# CAN-Bus.net
KiCad netlist of a schematic drawn in EAGLE
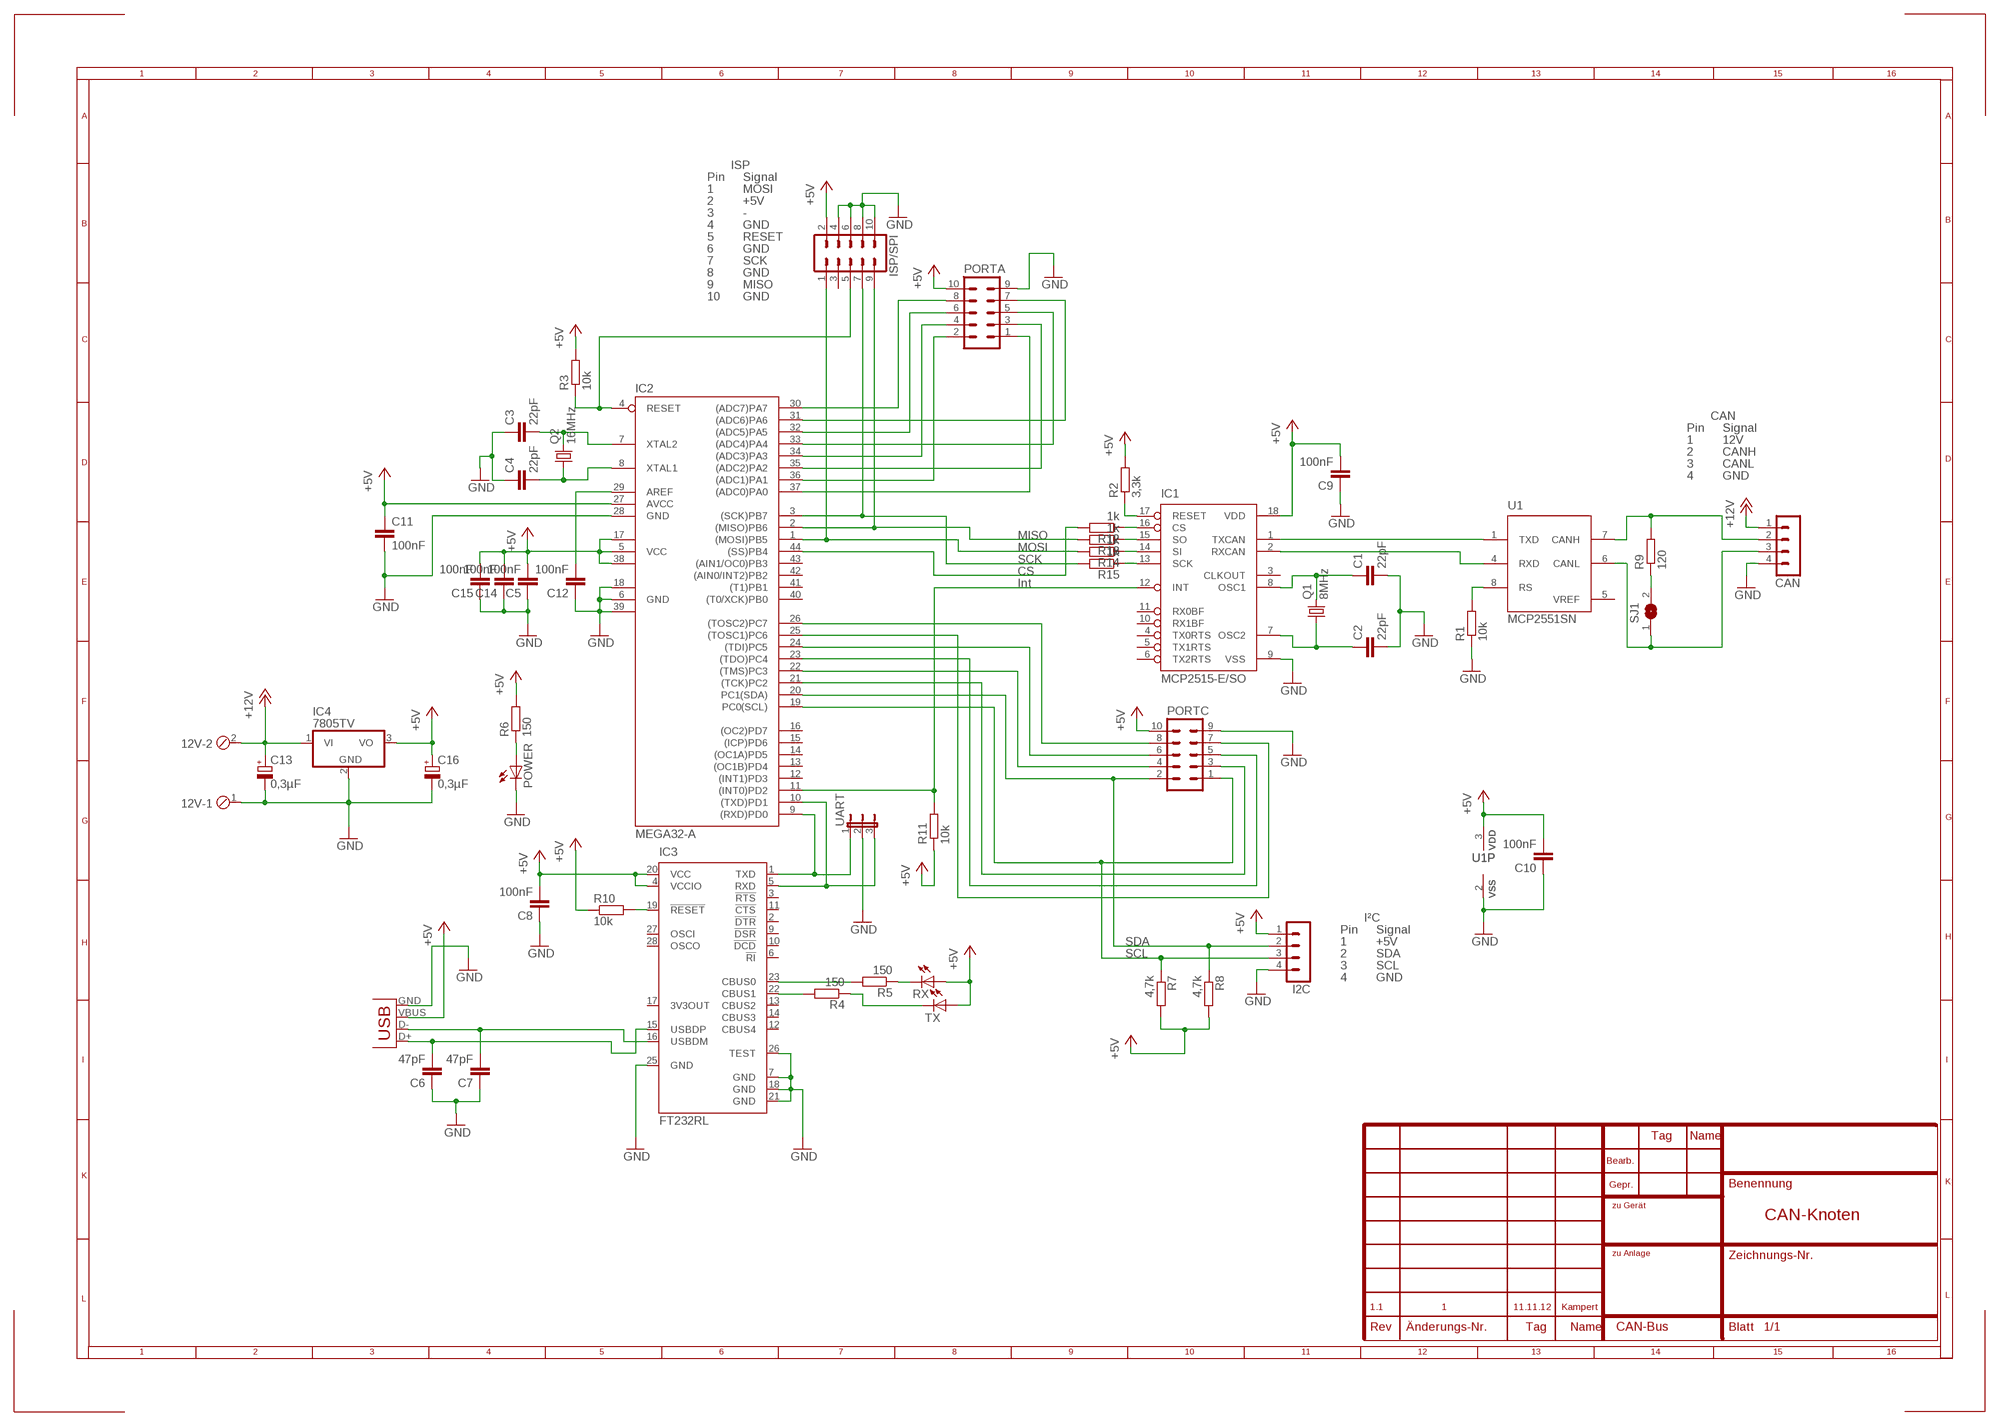
[diagram p0: schematic, sheet 1]

(export (version "E")
  (design (tool "Eeschema 10.0.6"))
  (components
    (comp (ref "12V")
      (value "MPT2")
      (footprint "eagle-import:2POL254")
      (libsource (lib "eagle-import") (part "MPT2"))
    )
    (comp (ref "C1")
      (value "22pF")
      (footprint "eagle-import:C0805")
      (libsource (lib "eagle-import") (part "C-EUC0805"))
    )
    (comp (ref "C2")
      (value "22pF")
      (footprint "eagle-import:C0805")
      (libsource (lib "eagle-import") (part "C-EUC0805"))
    )
    (comp (ref "C3")
      (value "22pF")
      (footprint "eagle-import:C0805")
      (libsource (lib "eagle-import") (part "C-EUC0805"))
    )
    (comp (ref "C4")
      (value "22pF")
      (footprint "eagle-import:C0805")
      (libsource (lib "eagle-import") (part "C-EUC0805"))
    )
    (comp (ref "C5")
      (value "100nF")
      (footprint "eagle-import:C0805")
      (libsource (lib "eagle-import") (part "C-EUC0805"))
    )
    (comp (ref "C6")
      (value "47pF")
      (footprint "eagle-import:C0805")
      (libsource (lib "eagle-import") (part "C-EUC0805"))
    )
    (comp (ref "C7")
      (value "47pF")
      (footprint "eagle-import:C0805")
      (libsource (lib "eagle-import") (part "C-EUC0805"))
    )
    (comp (ref "C8")
      (value "100nF")
      (footprint "eagle-import:C0805")
      (libsource (lib "eagle-import") (part "C-EUC0805"))
    )
    (comp (ref "C9")
      (value "100nF")
      (footprint "eagle-import:C0805")
      (libsource (lib "eagle-import") (part "C-EUC0805"))
    )
    (comp (ref "C10")
      (value "100nF")
      (footprint "eagle-import:C0805")
      (libsource (lib "eagle-import") (part "C-EUC0805"))
    )
    (comp (ref "C11")
      (value "100nF")
      (footprint "eagle-import:C0805")
      (libsource (lib "eagle-import") (part "C-EUC0805"))
    )
    (comp (ref "C12")
      (value "100nF")
      (footprint "eagle-import:C0805")
      (libsource (lib "eagle-import") (part "C-EUC0805"))
    )
    (comp (ref "C13")
      (value "0,3µF")
      (footprint "eagle-import:153CLV-0405")
      (libsource (lib "eagle-import") (part "CPOL-EU153CLV-0405"))
    )
    (comp (ref "C14")
      (value "100nF")
      (footprint "eagle-import:C0805")
      (libsource (lib "eagle-import") (part "C-EUC0805"))
    )
    (comp (ref "C15")
      (value "100nF")
      (footprint "eagle-import:C0805")
      (libsource (lib "eagle-import") (part "C-EUC0805"))
    )
    (comp (ref "C16")
      (value "0,3µF")
      (footprint "eagle-import:153CLV-0405")
      (libsource (lib "eagle-import") (part "CPOL-EU153CLV-0405"))
    )
    (comp (ref "CAN")
      (value "MA04-1")
      (footprint "eagle-import:MA04-1")
      (libsource (lib "eagle-import") (part "MA04-1"))
    )
    (comp (ref "I2C")
      (value "MA04-1")
      (footprint "eagle-import:MA04-1")
      (fields (field (name "OC_FARNELL") "unknown") (field (name "OC_NEWARK") "unknown"))
      (libsource (lib "eagle-import") (part "MA04-1"))
    )
    (comp (ref "IC1")
      (value "MCP2515-E/SO")
      (footprint "eagle-import:SO18L")
      (libsource (lib "eagle-import") (part "MCP2515-E/SO"))
    )
    (comp (ref "IC2")
      (value "MEGA32-A")
      (footprint "eagle-import:TQFP44")
      (fields (field (name "MPN") "ATMEGA32-16AU"))
      (libsource (lib "eagle-import") (part "MEGA32-A"))
    )
    (comp (ref "IC3")
      (value "FT232RL")
      (footprint "eagle-import:SSOP28")
      (libsource (lib "eagle-import") (part "FT232RL"))
    )
    (comp (ref "IC4")
      (value "7805TV")
      (footprint "eagle-import:TO220V")
      (libsource (lib "eagle-import") (part "78TV05"))
    )
    (comp (ref "ISP/SPI")
      (value "ML10")
      (footprint "eagle-import:ML10")
      (libsource (lib "eagle-import") (part "ML10"))
    )
    (comp (ref "PORTA")
      (value "ML10")
      (footprint "eagle-import:ML10")
      (fields (field (name "OC_FARNELL") "unknown") (field (name "OC_NEWARK") "unknown"))
      (libsource (lib "eagle-import") (part "ML10"))
    )
    (comp (ref "PORTC")
      (value "ML10")
      (footprint "eagle-import:ML10")
      (fields (field (name "OC_FARNELL") "unknown") (field (name "OC_NEWARK") "unknown"))
      (libsource (lib "eagle-import") (part "ML10"))
    )
    (comp (ref "POWER")
      (value "LEDCHIP-LED0805")
      (footprint "eagle-import:CHIP-LED0805")
      (libsource (lib "eagle-import") (part "LEDCHIP-LED0805"))
    )
    (comp (ref "Q1")
      (value "8MHz")
      (footprint "eagle-import:HC49UP")
      (libsource (lib "eagle-import") (part "CRYSTALHC49UP"))
    )
    (comp (ref "Q2")
      (value "16MHz")
      (footprint "eagle-import:HC49UP")
      (libsource (lib "eagle-import") (part "CRYSTALHC49UP"))
    )
    (comp (ref "R1")
      (value "10k")
      (footprint "eagle-import:M0805")
      (libsource (lib "eagle-import") (part "R-EU_M0805"))
    )
    (comp (ref "R2")
      (value "3,3k")
      (footprint "eagle-import:M0805")
      (libsource (lib "eagle-import") (part "R-EU_M0805"))
    )
    (comp (ref "R3")
      (value "10k")
      (footprint "eagle-import:M0805")
      (libsource (lib "eagle-import") (part "R-EU_M0805"))
    )
    (comp (ref "R4")
      (value "150")
      (footprint "eagle-import:M0805")
      (libsource (lib "eagle-import") (part "R-EU_M0805"))
    )
    (comp (ref "R5")
      (value "150")
      (footprint "eagle-import:M0805")
      (libsource (lib "eagle-import") (part "R-EU_M0805"))
    )
    (comp (ref "R6")
      (value "150")
      (footprint "eagle-import:M0805")
      (libsource (lib "eagle-import") (part "R-EU_M0805"))
    )
    (comp (ref "R7")
      (value "4,7k")
      (footprint "eagle-import:M0805")
      (libsource (lib "eagle-import") (part "R-EU_M0805"))
    )
    (comp (ref "R8")
      (value "4,7k")
      (footprint "eagle-import:M0805")
      (libsource (lib "eagle-import") (part "R-EU_M0805"))
    )
    (comp (ref "R9")
      (value "120")
      (footprint "eagle-import:M0805")
      (libsource (lib "eagle-import") (part "R-EU_M0805"))
    )
    (comp (ref "R10")
      (value "10k")
      (footprint "eagle-import:M0805")
      (libsource (lib "eagle-import") (part "R-EU_M0805"))
    )
    (comp (ref "R11")
      (value "10k")
      (footprint "eagle-import:M0805")
      (libsource (lib "eagle-import") (part "R-EU_M0805"))
    )
    (comp (ref "R12")
      (value "1k")
      (footprint "eagle-import:R0402")
      (libsource (lib "eagle-import") (part "R-EU_R0402"))
    )
    (comp (ref "R13")
      (value "1k")
      (footprint "eagle-import:R0402")
      (libsource (lib "eagle-import") (part "R-EU_R0402"))
    )
    (comp (ref "R14")
      (value "1k")
      (footprint "eagle-import:R0402")
      (libsource (lib "eagle-import") (part "R-EU_R0402"))
    )
    (comp (ref "R15")
      (value "1k")
      (footprint "eagle-import:R0402")
      (libsource (lib "eagle-import") (part "R-EU_R0402"))
    )
    (comp (ref "RX")
      (value "LEDCHIP-LED0805")
      (footprint "eagle-import:CHIP-LED0805")
      (libsource (lib "eagle-import") (part "LEDCHIP-LED0805"))
    )
    (comp (ref "SJ1") (value "SJ") (footprint "eagle-import:SJ") (libsource (lib "eagle-import") (part "SJ")))
    (comp (ref "TX")
      (value "LEDCHIP-LED0805")
      (footprint "eagle-import:CHIP-LED0805")
      (libsource (lib "eagle-import") (part "LEDCHIP-LED0805"))
    )
    (comp (ref "U1")
      (value "MCP2551SN")
      (footprint "eagle-import:SO-08")
      (libsource (lib "eagle-import") (part "MCP2551SN"))
    )
    (comp (ref "UART")
      (value "JP2E")
      (footprint "eagle-import:JP2")
      (libsource (lib "eagle-import") (part "JP2E"))
    )
    (comp (ref "X1")
      (value "USB-B-H")
      (footprint "eagle-import:USB-B-H")
      (libsource (lib "eagle-import") (part "USB-B-H"))
    )
  )
  (nets
    (net (code "1") (name "+5V") (class "Default")
      (node (ref "C10") (pin "2") (pinfunction "2_2") (pintype "passive"))
      (node (ref "C11") (pin "1") (pinfunction "1_1") (pintype "passive"))
      (node (ref "C14") (pin "2") (pinfunction "2_2") (pintype "passive"))
      (node (ref "C15") (pin "2") (pinfunction "2_2") (pintype "passive"))
      (node (ref "C16") (pin "+") (pinfunction "+_+") (pintype "passive"))
      (node (ref "C5") (pin "2") (pinfunction "2_2") (pintype "passive"))
      (node (ref "C8") (pin "2") (pinfunction "2_2") (pintype "passive"))
      (node (ref "C9") (pin "2") (pinfunction "2_2") (pintype "passive"))
      (node (ref "I2C") (pin "1") (pinfunction "1_1") (pintype "passive"))
      (node (ref "IC1") (pin "18") (pinfunction "VDD_18") (pintype "power_in"))
      (node (ref "IC2") (pin "17") (pinfunction "VCC1_17") (pintype "power_in"))
      (node (ref "IC2") (pin "27") (pinfunction "AVCC_27") (pintype "power_in"))
      (node (ref "IC2") (pin "38") (pinfunction "VCC2_38") (pintype "power_in"))
      (node (ref "IC2") (pin "5") (pinfunction "VCC_5") (pintype "power_in"))
      (node (ref "IC3") (pin "20") (pinfunction "VCC_20") (pintype "power_in"))
      (node (ref "IC3") (pin "4") (pinfunction "VCCIO_4") (pintype "power_in"))
      (node (ref "IC4") (pin "3") (pinfunction "VO_3") (pintype "passive"))
      (node (ref "ISP/SPI") (pin "2") (pinfunction "2_2") (pintype "passive"))
      (node (ref "PORTA") (pin "10") (pinfunction "10_10") (pintype "passive"))
      (node (ref "PORTC") (pin "10") (pinfunction "10_10") (pintype "passive"))
      (node (ref "R10") (pin "1") (pinfunction "1_1") (pintype "passive"))
      (node (ref "R11") (pin "1") (pinfunction "1_1") (pintype "passive"))
      (node (ref "R2") (pin "2") (pinfunction "2_2") (pintype "passive"))
      (node (ref "R3") (pin "2") (pinfunction "2_2") (pintype "passive"))
      (node (ref "R6") (pin "2") (pinfunction "2_2") (pintype "passive"))
      (node (ref "R7") (pin "2") (pinfunction "2_2") (pintype "passive"))
      (node (ref "R8") (pin "2") (pinfunction "2_2") (pintype "passive"))
      (node (ref "RX") (pin "A") (pinfunction "A_A") (pintype "passive"))
      (node (ref "TX") (pin "A") (pinfunction "A_A") (pintype "passive"))
      (node (ref "U1") (pin "3") (pinfunction "VDD_3") (pintype "power_in"))
      (node (ref "X1") (pin "VBUS") (pinfunction "VBUS_VBUS") (pintype "bidirectional"))
    )
    (net (code "2") (name "+12V") (class "Default")
      (node (ref "12V") (pin "2") (pinfunction "1_2") (pintype "passive"))
      (node (ref "C13") (pin "+") (pinfunction "+_+") (pintype "passive"))
      (node (ref "CAN") (pin "1") (pinfunction "1_1") (pintype "passive"))
      (node (ref "IC4") (pin "1") (pinfunction "VI_1") (pintype "input"))
    )
    (net (code "3") (name "/MOSI") (class "Default")
      (node (ref "IC2") (pin "1") (pinfunction "(MOSI)PB5_1") (pintype "bidirectional"))
      (node (ref "ISP/SPI") (pin "1") (pinfunction "1_1") (pintype "passive"))
      (node (ref "R14") (pin "2") (pinfunction "2_2") (pintype "passive"))
    )
    (net (code "4") (name "/VREF") (class "Default")
      (node (ref "U1") (pin "5") (pinfunction "VREF_5") (pintype "power_in"))
    )
    (net (code "5") (name "GND") (class "Default")
      (node (ref "12V") (pin "1") (pinfunction "1_1") (pintype "passive"))
      (node (ref "C1") (pin "2") (pinfunction "2_2") (pintype "passive"))
      (node (ref "C10") (pin "1") (pinfunction "1_1") (pintype "passive"))
      (node (ref "C11") (pin "2") (pinfunction "2_2") (pintype "passive"))
      (node (ref "C12") (pin "1") (pinfunction "1_1") (pintype "passive"))
      (node (ref "C13") (pin "-") (pinfunction "-_-") (pintype "passive"))
      (node (ref "C14") (pin "1") (pinfunction "1_1") (pintype "passive"))
      (node (ref "C15") (pin "1") (pinfunction "1_1") (pintype "passive"))
      (node (ref "C16") (pin "-") (pinfunction "-_-") (pintype "passive"))
      (node (ref "C2") (pin "2") (pinfunction "2_2") (pintype "passive"))
      (node (ref "C3") (pin "1") (pinfunction "1_1") (pintype "passive"))
      (node (ref "C4") (pin "1") (pinfunction "1_1") (pintype "passive"))
      (node (ref "C5") (pin "1") (pinfunction "1_1") (pintype "passive"))
      (node (ref "C6") (pin "1") (pinfunction "1_1") (pintype "passive"))
      (node (ref "C7") (pin "1") (pinfunction "1_1") (pintype "passive"))
      (node (ref "C8") (pin "1") (pinfunction "1_1") (pintype "passive"))
      (node (ref "C9") (pin "1") (pinfunction "1_1") (pintype "passive"))
      (node (ref "CAN") (pin "4") (pinfunction "4_4") (pintype "passive"))
      (node (ref "I2C") (pin "4") (pinfunction "4_4") (pintype "passive"))
      (node (ref "IC1") (pin "9") (pinfunction "VSS_9") (pintype "power_in"))
      (node (ref "IC2") (pin "18") (pinfunction "GND1_18") (pintype "power_in"))
      (node (ref "IC2") (pin "28") (pinfunction "GND_28") (pintype "power_in"))
      (node (ref "IC2") (pin "39") (pinfunction "GND2_39") (pintype "power_in"))
      (node (ref "IC2") (pin "6") (pinfunction "GND_6") (pintype "power_in"))
      (node (ref "IC3") (pin "18") (pinfunction "GND_18") (pintype "power_in"))
      (node (ref "IC3") (pin "21") (pinfunction "GND_21") (pintype "power_in"))
      (node (ref "IC3") (pin "25") (pinfunction "GND_25") (pintype "power_in"))
      (node (ref "IC3") (pin "26") (pinfunction "TEST_26") (pintype "input"))
      (node (ref "IC3") (pin "7") (pinfunction "GND_7") (pintype "power_in"))
      (node (ref "IC4") (pin "2") (pinfunction "GND_2") (pintype "passive"))
      (node (ref "ISP/SPI") (pin "10") (pinfunction "10_10") (pintype "passive"))
      (node (ref "ISP/SPI") (pin "4") (pinfunction "4_4") (pintype "passive"))
      (node (ref "ISP/SPI") (pin "6") (pinfunction "6_6") (pintype "passive"))
      (node (ref "ISP/SPI") (pin "8") (pinfunction "8_8") (pintype "passive"))
      (node (ref "PORTA") (pin "9") (pinfunction "9_9") (pintype "passive"))
      (node (ref "PORTC") (pin "9") (pinfunction "9_9") (pintype "passive"))
      (node (ref "POWER") (pin "C") (pinfunction "C_C") (pintype "passive"))
      (node (ref "R1") (pin "1") (pinfunction "1_1") (pintype "passive"))
      (node (ref "U1") (pin "2") (pinfunction "VSS_2") (pintype "power_in"))
      (node (ref "UART") (pin "2") (pinfunction "2_2") (pintype "passive"))
      (node (ref "X1") (pin "GND") (pinfunction "GND_GND") (pintype "bidirectional"))
    )
    (net (code "6") (name "Net-(IC1-CS)") (class "Default")
      (node (ref "IC1") (pin "16") (pinfunction "CS_16") (pintype "input"))
      (node (ref "R12") (pin "1") (pinfunction "1_1") (pintype "passive"))
    )
    (net (code "7") (name "Net-(IC1-INT)") (class "Default")
      (node (ref "IC1") (pin "12") (pinfunction "INT_12") (pintype "output"))
      (node (ref "IC2") (pin "11") (pinfunction "(INT0)PD2_11") (pintype "bidirectional"))
      (node (ref "R11") (pin "2") (pinfunction "2_2") (pintype "passive"))
    )
    (net (code "8") (name "Net-(IC1-OSC1)") (class "Default")
      (node (ref "C1") (pin "1") (pinfunction "1_1") (pintype "passive"))
      (node (ref "IC1") (pin "8") (pinfunction "OSC1_8") (pintype "input"))
      (node (ref "Q1") (pin "2") (pinfunction "2_2") (pintype "passive"))
    )
    (net (code "9") (name "Net-(IC1-OSC2)") (class "Default")
      (node (ref "C2") (pin "1") (pinfunction "1_1") (pintype "passive"))
      (node (ref "IC1") (pin "7") (pinfunction "OSC2_7") (pintype "output"))
      (node (ref "Q1") (pin "1") (pinfunction "1_1") (pintype "passive"))
    )
    (net (code "10") (name "Net-(IC1-RESET)") (class "Default")
      (node (ref "IC1") (pin "17") (pinfunction "RESET_17") (pintype "input"))
      (node (ref "R2") (pin "1") (pinfunction "1_1") (pintype "passive"))
    )
    (net (code "11") (name "Net-(IC1-RXCAN)") (class "Default")
      (node (ref "IC1") (pin "2") (pinfunction "RXCAN_2") (pintype "input"))
      (node (ref "U1") (pin "4") (pinfunction "RXD_4") (pintype "output"))
    )
    (net (code "12") (name "Net-(IC1-SCK)") (class "Default")
      (node (ref "IC1") (pin "13") (pinfunction "SCK_13") (pintype "input"))
      (node (ref "R15") (pin "1") (pinfunction "1_1") (pintype "passive"))
    )
    (net (code "13") (name "Net-(IC1-SI)") (class "Default")
      (node (ref "IC1") (pin "14") (pinfunction "SI_14") (pintype "input"))
      (node (ref "R14") (pin "1") (pinfunction "1_1") (pintype "passive"))
    )
    (net (code "14") (name "Net-(IC1-SO)") (class "Default")
      (node (ref "IC1") (pin "15") (pinfunction "SO_15") (pintype "output"))
      (node (ref "R13") (pin "1") (pinfunction "1_1") (pintype "passive"))
    )
    (net (code "15") (name "Net-(IC1-TXCAN)") (class "Default")
      (node (ref "IC1") (pin "1") (pinfunction "TXCAN_1") (pintype "output"))
      (node (ref "U1") (pin "1") (pinfunction "TXD_1") (pintype "input"))
    )
    (net (code "16") (name "Net-(IC2-(ADC0)PA0)") (class "Default")
      (node (ref "IC2") (pin "37") (pinfunction "(ADC0)PA0_37") (pintype "bidirectional"))
      (node (ref "PORTA") (pin "1") (pinfunction "1_1") (pintype "passive"))
    )
    (net (code "17") (name "Net-(IC2-(ADC1)PA1)") (class "Default")
      (node (ref "IC2") (pin "36") (pinfunction "(ADC1)PA1_36") (pintype "bidirectional"))
      (node (ref "PORTA") (pin "2") (pinfunction "2_2") (pintype "passive"))
    )
    (net (code "18") (name "Net-(IC2-(ADC2)PA2)") (class "Default")
      (node (ref "IC2") (pin "35") (pinfunction "(ADC2)PA2_35") (pintype "bidirectional"))
      (node (ref "PORTA") (pin "3") (pinfunction "3_3") (pintype "passive"))
    )
    (net (code "19") (name "Net-(IC2-(ADC3)PA3)") (class "Default")
      (node (ref "IC2") (pin "34") (pinfunction "(ADC3)PA3_34") (pintype "bidirectional"))
      (node (ref "PORTA") (pin "4") (pinfunction "4_4") (pintype "passive"))
    )
    (net (code "20") (name "Net-(IC2-(ADC4)PA4)") (class "Default")
      (node (ref "IC2") (pin "33") (pinfunction "(ADC4)PA4_33") (pintype "bidirectional"))
      (node (ref "PORTA") (pin "5") (pinfunction "5_5") (pintype "passive"))
    )
    (net (code "21") (name "Net-(IC2-(ADC5)PA5)") (class "Default")
      (node (ref "IC2") (pin "32") (pinfunction "(ADC5)PA5_32") (pintype "bidirectional"))
      (node (ref "PORTA") (pin "6") (pinfunction "6_6") (pintype "passive"))
    )
    (net (code "22") (name "Net-(IC2-(ADC6)PA6)") (class "Default")
      (node (ref "IC2") (pin "31") (pinfunction "(ADC6)PA6_31") (pintype "bidirectional"))
      (node (ref "PORTA") (pin "7") (pinfunction "7_7") (pintype "passive"))
    )
    (net (code "23") (name "Net-(IC2-(ADC7)PA7)") (class "Default")
      (node (ref "IC2") (pin "30") (pinfunction "(ADC7)PA7_30") (pintype "bidirectional"))
      (node (ref "PORTA") (pin "8") (pinfunction "8_8") (pintype "passive"))
    )
    (net (code "24") (name "Net-(IC2-(MISO)PB6)") (class "Default")
      (node (ref "IC2") (pin "2") (pinfunction "(MISO)PB6_2") (pintype "bidirectional"))
      (node (ref "ISP/SPI") (pin "9") (pinfunction "9_9") (pintype "passive"))
      (node (ref "R13") (pin "2") (pinfunction "2_2") (pintype "passive"))
    )
    (net (code "25") (name "Net-(IC2-(RXD)PD0)") (class "Default")
      (node (ref "IC2") (pin "9") (pinfunction "(RXD)PD0_9") (pintype "bidirectional"))
      (node (ref "IC3") (pin "1") (pinfunction "TXD_1") (pintype "output"))
      (node (ref "UART") (pin "1") (pinfunction "1_1") (pintype "passive"))
    )
    (net (code "26") (name "Net-(IC2-(SCK)PB7)") (class "Default")
      (node (ref "IC2") (pin "3") (pinfunction "(SCK)PB7_3") (pintype "bidirectional"))
      (node (ref "ISP/SPI") (pin "7") (pinfunction "7_7") (pintype "passive"))
      (node (ref "R15") (pin "2") (pinfunction "2_2") (pintype "passive"))
    )
    (net (code "27") (name "Net-(IC2-(SS)PB4)") (class "Default")
      (node (ref "IC2") (pin "44") (pinfunction "(SS)PB4_44") (pintype "bidirectional"))
      (node (ref "R12") (pin "2") (pinfunction "2_2") (pintype "passive"))
    )
    (net (code "28") (name "Net-(IC2-(TCK)PC2)") (class "Default")
      (node (ref "IC2") (pin "21") (pinfunction "(TCK)PC2_21") (pintype "bidirectional"))
      (node (ref "PORTC") (pin "3") (pinfunction "3_3") (pintype "passive"))
    )
    (net (code "29") (name "Net-(IC2-(TDI)PC5)") (class "Default")
      (node (ref "IC2") (pin "24") (pinfunction "(TDI)PC5_24") (pintype "bidirectional"))
      (node (ref "PORTC") (pin "6") (pinfunction "6_6") (pintype "passive"))
    )
    (net (code "30") (name "Net-(IC2-(TDO)PC4)") (class "Default")
      (node (ref "IC2") (pin "23") (pinfunction "(TDO)PC4_23") (pintype "bidirectional"))
      (node (ref "PORTC") (pin "5") (pinfunction "5_5") (pintype "passive"))
    )
    (net (code "31") (name "Net-(IC2-(TMS)PC3)") (class "Default")
      (node (ref "IC2") (pin "22") (pinfunction "(TMS)PC3_22") (pintype "bidirectional"))
      (node (ref "PORTC") (pin "4") (pinfunction "4_4") (pintype "passive"))
    )
    (net (code "32") (name "Net-(IC2-(TOSC1)PC6)") (class "Default")
      (node (ref "IC2") (pin "25") (pinfunction "(TOSC1)PC6_25") (pintype "bidirectional"))
      (node (ref "PORTC") (pin "7") (pinfunction "7_7") (pintype "passive"))
    )
    (net (code "33") (name "Net-(IC2-(TOSC2)PC7)") (class "Default")
      (node (ref "IC2") (pin "26") (pinfunction "(TOSC2)PC7_26") (pintype "bidirectional"))
      (node (ref "PORTC") (pin "8") (pinfunction "8_8") (pintype "passive"))
    )
    (net (code "34") (name "Net-(IC2-(TXD)PD1)") (class "Default")
      (node (ref "IC2") (pin "10") (pinfunction "(TXD)PD1_10") (pintype "bidirectional"))
      (node (ref "IC3") (pin "5") (pinfunction "RXD_5") (pintype "input"))
      (node (ref "UART") (pin "3") (pinfunction "3_3") (pintype "passive"))
    )
    (net (code "35") (name "Net-(IC2-AREF)") (class "Default")
      (node (ref "C12") (pin "2") (pinfunction "2_2") (pintype "passive"))
      (node (ref "IC2") (pin "29") (pinfunction "AREF_29") (pintype "passive"))
    )
    (net (code "36") (name "Net-(IC2-PC0(SCL))") (class "Default")
      (node (ref "I2C") (pin "3") (pinfunction "3_3") (pintype "passive"))
      (node (ref "IC2") (pin "19") (pinfunction "PC0(SCL)_19") (pintype "bidirectional"))
      (node (ref "PORTC") (pin "1") (pinfunction "1_1") (pintype "passive"))
      (node (ref "R7") (pin "1") (pinfunction "1_1") (pintype "passive"))
    )
    (net (code "37") (name "Net-(IC2-PC1(SDA))") (class "Default")
      (node (ref "I2C") (pin "2") (pinfunction "2_2") (pintype "passive"))
      (node (ref "IC2") (pin "20") (pinfunction "PC1(SDA)_20") (pintype "bidirectional"))
      (node (ref "PORTC") (pin "2") (pinfunction "2_2") (pintype "passive"))
      (node (ref "R8") (pin "1") (pinfunction "1_1") (pintype "passive"))
    )
    (net (code "38") (name "Net-(IC2-RESET)") (class "Default")
      (node (ref "IC2") (pin "4") (pinfunction "RESET_4") (pintype "input"))
      (node (ref "ISP/SPI") (pin "5") (pinfunction "5_5") (pintype "passive"))
      (node (ref "R3") (pin "1") (pinfunction "1_1") (pintype "passive"))
    )
    (net (code "39") (name "Net-(IC2-XTAL1)") (class "Default")
      (node (ref "C4") (pin "2") (pinfunction "2_2") (pintype "passive"))
      (node (ref "IC2") (pin "8") (pinfunction "XTAL1_8") (pintype "bidirectional"))
      (node (ref "Q2") (pin "1") (pinfunction "1_1") (pintype "passive"))
    )
    (net (code "40") (name "Net-(IC2-XTAL2)") (class "Default")
      (node (ref "C3") (pin "2") (pinfunction "2_2") (pintype "passive"))
      (node (ref "IC2") (pin "7") (pinfunction "XTAL2_7") (pintype "bidirectional"))
      (node (ref "Q2") (pin "2") (pinfunction "2_2") (pintype "passive"))
    )
    (net (code "41") (name "Net-(IC3-CBUS0)") (class "Default")
      (node (ref "IC3") (pin "23") (pinfunction "CBUS0_23") (pintype "bidirectional"))
      (node (ref "R5") (pin "2") (pinfunction "2_2") (pintype "passive"))
    )
    (net (code "42") (name "Net-(IC3-CBUS1)") (class "Default")
      (node (ref "IC3") (pin "22") (pinfunction "CBUS1_22") (pintype "bidirectional"))
      (node (ref "R4") (pin "2") (pinfunction "2_2") (pintype "passive"))
    )
    (net (code "43") (name "Net-(IC3-USBDM)") (class "Default")
      (node (ref "C7") (pin "2") (pinfunction "2_2") (pintype "passive"))
      (node (ref "IC3") (pin "16") (pinfunction "USBDM_16") (pintype "bidirectional"))
      (node (ref "X1") (pin "D-") (pinfunction "D-_D-") (pintype "bidirectional"))
    )
    (net (code "44") (name "Net-(IC3-USBDP)") (class "Default")
      (node (ref "C6") (pin "2") (pinfunction "2_2") (pintype "passive"))
      (node (ref "IC3") (pin "15") (pinfunction "USBDP_15") (pintype "bidirectional"))
      (node (ref "X1") (pin "D+") (pinfunction "D+_D+") (pintype "bidirectional"))
    )
    (net (code "45") (name "Net-(IC3-~{RESET})") (class "Default")
      (node (ref "IC3") (pin "19") (pinfunction "~{RESET}_19") (pintype "input"))
      (node (ref "R10") (pin "2") (pinfunction "2_2") (pintype "passive"))
    )
    (net (code "46") (name "Net-(POWER-PadA)") (class "Default")
      (node (ref "POWER") (pin "A") (pinfunction "A_A") (pintype "passive"))
      (node (ref "R6") (pin "1") (pinfunction "1_1") (pintype "passive"))
    )
    (net (code "47") (name "Net-(R4-Pad1)") (class "Default")
      (node (ref "R4") (pin "1") (pinfunction "1_1") (pintype "passive"))
      (node (ref "TX") (pin "C") (pinfunction "C_C") (pintype "passive"))
    )
    (net (code "48") (name "Net-(R5-Pad1)") (class "Default")
      (node (ref "R5") (pin "1") (pinfunction "1_1") (pintype "passive"))
      (node (ref "RX") (pin "C") (pinfunction "C_C") (pintype "passive"))
    )
    (net (code "49") (name "Net-(R9-Pad1)") (class "Default")
      (node (ref "R9") (pin "1") (pinfunction "1_1") (pintype "passive"))
      (node (ref "SJ1") (pin "2") (pinfunction "2_2") (pintype "passive"))
    )
    (net (code "50") (name "Net-(U1A-CANH)") (class "Default")
      (node (ref "CAN") (pin "2") (pinfunction "2_2") (pintype "passive"))
      (node (ref "R9") (pin "2") (pinfunction "2_2") (pintype "passive"))
      (node (ref "U1") (pin "7") (pinfunction "CANH_7") (pintype "bidirectional"))
    )
    (net (code "51") (name "Net-(U1A-CANL)") (class "Default")
      (node (ref "CAN") (pin "3") (pinfunction "3_3") (pintype "passive"))
      (node (ref "SJ1") (pin "1") (pinfunction "1_1") (pintype "passive"))
      (node (ref "U1") (pin "6") (pinfunction "CANL_6") (pintype "bidirectional"))
    )
    (net (code "52") (name "Net-(U1A-RS)") (class "Default")
      (node (ref "R1") (pin "2") (pinfunction "2_2") (pintype "passive"))
      (node (ref "U1") (pin "8") (pinfunction "RS_8") (pintype "input"))
    )
    (net (code "53") (name "unconnected-(IC1-CLKOUT-Pad3)") (class "Default")
      (node (ref "IC1") (pin "3") (pinfunction "CLKOUT_3") (pintype "output"))
    )
    (net (code "54") (name "unconnected-(IC1-RX0BF-Pad11)") (class "Default")
      (node (ref "IC1") (pin "11") (pinfunction "RX0BF_11") (pintype "output"))
    )
    (net (code "55") (name "unconnected-(IC1-RX1BF-Pad10)") (class "Default")
      (node (ref "IC1") (pin "10") (pinfunction "RX1BF_10") (pintype "output"))
    )
    (net (code "56") (name "unconnected-(IC1-TX0RTS-Pad4)") (class "Default")
      (node (ref "IC1") (pin "4") (pinfunction "TX0RTS_4") (pintype "input"))
    )
    (net (code "57") (name "unconnected-(IC1-TX1RTS-Pad5)") (class "Default")
      (node (ref "IC1") (pin "5") (pinfunction "TX1RTS_5") (pintype "input"))
    )
    (net (code "58") (name "unconnected-(IC1-TX2RTS-Pad6)") (class "Default")
      (node (ref "IC1") (pin "6") (pinfunction "TX2RTS_6") (pintype "input"))
    )
    (net (code "59") (name "unconnected-(IC2-(AIN0{slash}INT2)PB2-Pad42)") (class "Default")
      (node (ref "IC2") (pin "42") (pinfunction "(AIN0/INT2)PB2_42") (pintype "bidirectional"))
    )
    (net (code "60") (name "unconnected-(IC2-(AIN1{slash}OC0)PB3-Pad43)") (class "Default")
      (node (ref "IC2") (pin "43") (pinfunction "(AIN1/OC0)PB3_43") (pintype "bidirectional"))
    )
    (net (code "61") (name "unconnected-(IC2-(ICP)PD6-Pad15)") (class "Default")
      (node (ref "IC2") (pin "15") (pinfunction "(ICP)PD6_15") (pintype "bidirectional"))
    )
    (net (code "62") (name "unconnected-(IC2-(INT1)PD3-Pad12)") (class "Default")
      (node (ref "IC2") (pin "12") (pinfunction "(INT1)PD3_12") (pintype "bidirectional"))
    )
    (net (code "63") (name "unconnected-(IC2-(OC1A)PD5-Pad14)") (class "Default")
      (node (ref "IC2") (pin "14") (pinfunction "(OC1A)PD5_14") (pintype "bidirectional"))
    )
    (net (code "64") (name "unconnected-(IC2-(OC1B)PD4-Pad13)") (class "Default")
      (node (ref "IC2") (pin "13") (pinfunction "(OC1B)PD4_13") (pintype "bidirectional"))
    )
    (net (code "65") (name "unconnected-(IC2-(OC2)PD7-Pad16)") (class "Default")
      (node (ref "IC2") (pin "16") (pinfunction "(OC2)PD7_16") (pintype "bidirectional"))
    )
    (net (code "66") (name "unconnected-(IC2-(T0{slash}XCK)PB0-Pad40)") (class "Default")
      (node (ref "IC2") (pin "40") (pinfunction "(T0/XCK)PB0_40") (pintype "bidirectional"))
    )
    (net (code "67") (name "unconnected-(IC2-(T1)PB1-Pad41)") (class "Default")
      (node (ref "IC2") (pin "41") (pinfunction "(T1)PB1_41") (pintype "bidirectional"))
    )
    (net (code "68") (name "unconnected-(IC3-3V3OUT-Pad17)") (class "Default")
      (node (ref "IC3") (pin "17") (pinfunction "3V3OUT_17") (pintype "output"))
    )
    (net (code "69") (name "unconnected-(IC3-CBUS2-Pad13)") (class "Default")
      (node (ref "IC3") (pin "13") (pinfunction "CBUS2_13") (pintype "bidirectional"))
    )
    (net (code "70") (name "unconnected-(IC3-CBUS3-Pad14)") (class "Default")
      (node (ref "IC3") (pin "14") (pinfunction "CBUS3_14") (pintype "bidirectional"))
    )
    (net (code "71") (name "unconnected-(IC3-CBUS4-Pad12)") (class "Default")
      (node (ref "IC3") (pin "12") (pinfunction "CBUS4_12") (pintype "bidirectional"))
    )
    (net (code "72") (name "unconnected-(IC3-OSCI-Pad27)") (class "Default")
      (node (ref "IC3") (pin "27") (pinfunction "OSCI_27") (pintype "input"))
    )
    (net (code "73") (name "unconnected-(IC3-OSCO-Pad28)") (class "Default")
      (node (ref "IC3") (pin "28") (pinfunction "OSCO_28") (pintype "output"))
    )
    (net (code "74") (name "unconnected-(IC3-~{CTS}-Pad11)") (class "Default")
      (node (ref "IC3") (pin "11") (pinfunction "~{CTS}_11") (pintype "input"))
    )
    (net (code "75") (name "unconnected-(IC3-~{DCD}-Pad10)") (class "Default")
      (node (ref "IC3") (pin "10") (pinfunction "~{DCD}_10") (pintype "input"))
    )
    (net (code "76") (name "unconnected-(IC3-~{DSR}-Pad9)") (class "Default")
      (node (ref "IC3") (pin "9") (pinfunction "~{DSR}_9") (pintype "input"))
    )
    (net (code "77") (name "unconnected-(IC3-~{DTR}-Pad2)") (class "Default")
      (node (ref "IC3") (pin "2") (pinfunction "~{DTR}_2") (pintype "output"))
    )
    (net (code "78") (name "unconnected-(IC3-~{RI}-Pad6)") (class "Default")
      (node (ref "IC3") (pin "6") (pinfunction "~{RI}_6") (pintype "input"))
    )
    (net (code "79") (name "unconnected-(IC3-~{RTS}-Pad3)") (class "Default")
      (node (ref "IC3") (pin "3") (pinfunction "~{RTS}_3") (pintype "output"))
    )
    (net (code "80") (name "unconnected-(ISP/SPI-Pad3)") (class "Default")
      (node (ref "ISP/SPI") (pin "3") (pinfunction "3_3") (pintype "passive"))
    )
  )
)
